# Sch_LVTN.net
KiCad netlist of a schematic drawn in Altium Designer
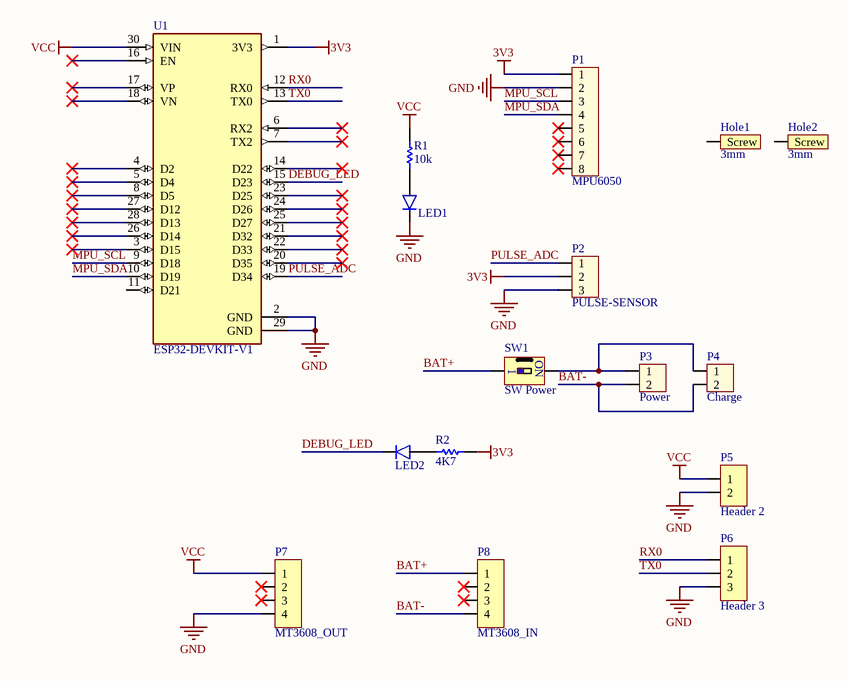
[diagram p0: Sch_LVTN.SchDoc]

(export (version "E")
  (design (tool "Eeschema 10.0.6"))
  (components
    (comp (ref "Hole1") (value "3mm") (footprint "SCREW/3M/7M") (libsource (lib "BKIT4U_LIB") (part "Screw")))
    (comp (ref "Hole2") (value "3mm") (footprint "SCREW/3M/7M") (libsource (lib "BKIT4U_LIB") (part "Screw")))
    (comp (ref "LED1")
      (value "Led")
      (footprint "Led SMD 0805")
      (description "Typical LED")
      (libsource (lib "BKIT4U_LIB") (part "Led"))
    )
    (comp (ref "LED2")
      (value "Led")
      (footprint "Led SMD 0805")
      (description "Typical LED")
      (libsource (lib "BKIT4U_LIB") (part "Led"))
    )
    (comp (ref "P1")
      (value "MPU6050")
      (footprint "CON Header 8")
      (description "Connector 8")
      (libsource (lib "BKIT4U_LIB") (part "Con8"))
    )
    (comp (ref "P2")
      (value "PULSE-SENSOR")
      (footprint "CON Header 3")
      (description "Connector 3")
      (libsource (lib "BKIT4U_LIB") (part "Con3"))
    )
    (comp (ref "P3")
      (value "Power")
      (footprint "CON Header 2")
      (description "Connector 2")
      (libsource (lib "BKIT4U_LIB") (part "Con2"))
    )
    (comp (ref "P4")
      (value "Charge")
      (footprint "CON Header 2 - RA")
      (description "Connector 2")
      (libsource (lib "BKIT4U_LIB") (part "Con2"))
    )
    (comp (ref "P5")
      (value "Header 2")
      (footprint "Header 2")
      (description "Header, 2-Pin")
      (fields (field (name "PUBLISHER") "Altium Limited"))
      (libsource (lib "BKIT4U_LIB") (part "Header 2"))
    )
    (comp (ref "P6")
      (value "Header 3")
      (footprint "Header 3")
      (description "Header, 3-Pin")
      (libsource (lib "BKIT4U_LIB") (part "Header 3"))
    )
    (comp (ref "P7")
      (value "MT3608_OUT")
      (footprint "Header 4")
      (description "Header, 4-Pin")
      (libsource (lib "BKIT4U_LIB") (part "Header 4"))
    )
    (comp (ref "P8")
      (value "MT3608_IN")
      (footprint "Header 4")
      (description "Header, 4-Pin")
      (libsource (lib "BKIT4U_LIB") (part "Header 4"))
    )
    (comp (ref "R1")
      (value "10k")
      (footprint "R 0805 (2012)")
      (description "Resistor")
      (fields (field (name "PUBLISHER") "Altium Limited"))
      (libsource (lib "BKIT4U_LIB") (part "Resistor"))
    )
    (comp (ref "R2")
      (value "4K7")
      (footprint "R 0805 (2012)")
      (description "Resistor")
      (fields (field (name "PUBLISHER") "Altium Limited"))
      (libsource (lib "BKIT4U_LIB") (part "Resistor"))
    )
    (comp (ref "SW1")
      (value "SW Power")
      (footprint "SW/DIP1")
      (libsource (lib "BKIT4U_LIB") (part "SW DIP-1"))
    )
    (comp (ref "U1")
      (value "ESP32-DEVKIT-V1")
      (footprint "MODULE_ESP32_DEVKIT_V1")
      (fields (field (name "MF") "Do it"))
      (libsource (lib "ESP32-DEVKIT-V1") (part "ESP32-DEVKIT-V1"))
    )
  )
  (nets
    (net (code "1") (name "/BAT+") (class "Default")
      (node (ref "P8") (pin "1") (pinfunction "1_1") (pintype "passive"))
      (node (ref "SW1") (pin "1") (pinfunction "1_1") (pintype "passive"))
    )
    (net (code "2") (name "/BAT-") (class "Default")
      (node (ref "P3") (pin "2") (pinfunction "2_2") (pintype "passive"))
      (node (ref "P4") (pin "2") (pinfunction "2_2") (pintype "passive"))
      (node (ref "P8") (pin "4") (pinfunction "4_4") (pintype "passive"))
    )
    (net (code "3") (name "/DEBUG_LED") (class "Default")
      (node (ref "LED2") (pin "2") (pinfunction "K_2") (pintype "passive"))
      (node (ref "U1") (pin "15") (pinfunction "D23_15") (pintype "bidirectional"))
    )
    (net (code "4") (name "/MPU_SCL") (class "Default")
      (node (ref "P1") (pin "3") (pinfunction "3_3") (pintype "passive"))
      (node (ref "U1") (pin "9") (pinfunction "D18_9") (pintype "bidirectional"))
    )
    (net (code "5") (name "/MPU_SDA") (class "Default")
      (node (ref "P1") (pin "4") (pinfunction "4_4") (pintype "passive"))
      (node (ref "U1") (pin "10") (pinfunction "D19_10") (pintype "bidirectional"))
    )
    (net (code "6") (name "/PULSE_ADC") (class "Default")
      (node (ref "P2") (pin "1") (pinfunction "1_1") (pintype "passive"))
      (node (ref "U1") (pin "19") (pinfunction "D34_19") (pintype "bidirectional"))
    )
    (net (code "7") (name "/RX0") (class "Default")
      (node (ref "P6") (pin "1") (pinfunction "1_1") (pintype "passive"))
      (node (ref "U1") (pin "12") (pinfunction "RX0_12") (pintype "input"))
    )
    (net (code "8") (name "/TX0") (class "Default")
      (node (ref "P6") (pin "2") (pinfunction "2_2") (pintype "passive"))
      (node (ref "U1") (pin "13") (pinfunction "TX0_13") (pintype "output"))
    )
    (net (code "9") (name "3V3") (class "Default")
      (node (ref "P1") (pin "1") (pinfunction "1_1") (pintype "passive"))
      (node (ref "P2") (pin "2") (pinfunction "2_2") (pintype "passive"))
      (node (ref "R2") (pin "2") (pinfunction "2_2") (pintype "passive"))
      (node (ref "U1") (pin "1") (pinfunction "3V3_1") (pintype "output"))
    )
    (net (code "10") (name "GND") (class "Default")
      (node (ref "LED1") (pin "2") (pinfunction "K_2") (pintype "passive"))
      (node (ref "P1") (pin "2") (pinfunction "2_2") (pintype "passive"))
      (node (ref "P2") (pin "3") (pinfunction "3_3") (pintype "passive"))
      (node (ref "P5") (pin "2") (pinfunction "2_2") (pintype "passive"))
      (node (ref "P6") (pin "3") (pinfunction "3_3") (pintype "passive"))
      (node (ref "P7") (pin "4") (pinfunction "4_4") (pintype "passive"))
      (node (ref "U1") (pin "2") (pinfunction "GND_2") (pintype "power_in"))
      (node (ref "U1") (pin "29") (pinfunction "GND_29") (pintype "power_in"))
    )
    (net (code "11") (name "Net-(LED1-A)") (class "Default")
      (node (ref "LED1") (pin "1") (pinfunction "A_1") (pintype "passive"))
      (node (ref "R1") (pin "1") (pinfunction "1_1") (pintype "passive"))
    )
    (net (code "12") (name "Net-(LED2-A)") (class "Default")
      (node (ref "LED2") (pin "1") (pinfunction "A_1") (pintype "passive"))
      (node (ref "R2") (pin "1") (pinfunction "1_1") (pintype "passive"))
    )
    (net (code "13") (name "Net-(P3-Pad1)") (class "Default")
      (node (ref "P3") (pin "1") (pinfunction "1_1") (pintype "passive"))
      (node (ref "P4") (pin "1") (pinfunction "1_1") (pintype "passive"))
      (node (ref "SW1") (pin "2") (pinfunction "2_2") (pintype "passive"))
    )
    (net (code "14") (name "VCC") (class "Default")
      (node (ref "P5") (pin "1") (pinfunction "1_1") (pintype "passive"))
      (node (ref "P7") (pin "1") (pinfunction "1_1") (pintype "passive"))
      (node (ref "R1") (pin "2") (pinfunction "2_2") (pintype "passive"))
      (node (ref "U1") (pin "30") (pinfunction "VIN_30") (pintype "input"))
    )
    (net (code "15") (name "unconnected-(Hole1-Screw-Pad1)") (class "Default")
      (node (ref "Hole1") (pin "1") (pinfunction "Screw_1") (pintype "passive"))
    )
    (net (code "16") (name "unconnected-(Hole2-Screw-Pad1)") (class "Default")
      (node (ref "Hole2") (pin "1") (pinfunction "Screw_1") (pintype "passive"))
    )
    (net (code "17") (name "unconnected-(P1-Pad5)") (class "Default")
      (node (ref "P1") (pin "5") (pinfunction "5_5") (pintype "passive+no_connect"))
    )
    (net (code "18") (name "unconnected-(P1-Pad6)") (class "Default")
      (node (ref "P1") (pin "6") (pinfunction "6_6") (pintype "passive+no_connect"))
    )
    (net (code "19") (name "unconnected-(P1-Pad7)") (class "Default")
      (node (ref "P1") (pin "7") (pinfunction "7_7") (pintype "passive+no_connect"))
    )
    (net (code "20") (name "unconnected-(P1-Pad8)") (class "Default")
      (node (ref "P1") (pin "8") (pinfunction "8_8") (pintype "passive+no_connect"))
    )
    (net (code "21") (name "unconnected-(P7-Pad2)") (class "Default")
      (node (ref "P7") (pin "2") (pinfunction "2_2") (pintype "passive+no_connect"))
    )
    (net (code "22") (name "unconnected-(P7-Pad3)") (class "Default")
      (node (ref "P7") (pin "3") (pinfunction "3_3") (pintype "passive+no_connect"))
    )
    (net (code "23") (name "unconnected-(P8-Pad2)") (class "Default")
      (node (ref "P8") (pin "2") (pinfunction "2_2") (pintype "passive+no_connect"))
    )
    (net (code "24") (name "unconnected-(P8-Pad3)") (class "Default")
      (node (ref "P8") (pin "3") (pinfunction "3_3") (pintype "passive+no_connect"))
    )
    (net (code "25") (name "unconnected-(U1-D2-Pad4)") (class "Default")
      (node (ref "U1") (pin "4") (pinfunction "D2_4") (pintype "bidirectional+no_connect"))
    )
    (net (code "26") (name "unconnected-(U1-D4-Pad5)") (class "Default")
      (node (ref "U1") (pin "5") (pinfunction "D4_5") (pintype "bidirectional+no_connect"))
    )
    (net (code "27") (name "unconnected-(U1-D5-Pad8)") (class "Default")
      (node (ref "U1") (pin "8") (pinfunction "D5_8") (pintype "bidirectional+no_connect"))
    )
    (net (code "28") (name "unconnected-(U1-D12-Pad27)") (class "Default")
      (node (ref "U1") (pin "27") (pinfunction "D12_27") (pintype "bidirectional+no_connect"))
    )
    (net (code "29") (name "unconnected-(U1-D13-Pad28)") (class "Default")
      (node (ref "U1") (pin "28") (pinfunction "D13_28") (pintype "bidirectional+no_connect"))
    )
    (net (code "30") (name "unconnected-(U1-D14-Pad26)") (class "Default")
      (node (ref "U1") (pin "26") (pinfunction "D14_26") (pintype "bidirectional+no_connect"))
    )
    (net (code "31") (name "unconnected-(U1-D15-Pad3)") (class "Default")
      (node (ref "U1") (pin "3") (pinfunction "D15_3") (pintype "bidirectional+no_connect"))
    )
    (net (code "32") (name "unconnected-(U1-D21-Pad11)") (class "Default")
      (node (ref "U1") (pin "11") (pinfunction "D21_11") (pintype "bidirectional"))
    )
    (net (code "33") (name "unconnected-(U1-D22-Pad14)") (class "Default")
      (node (ref "U1") (pin "14") (pinfunction "D22_14") (pintype "bidirectional+no_connect"))
    )
    (net (code "34") (name "unconnected-(U1-D25-Pad23)") (class "Default")
      (node (ref "U1") (pin "23") (pinfunction "D25_23") (pintype "bidirectional+no_connect"))
    )
    (net (code "35") (name "unconnected-(U1-D26-Pad24)") (class "Default")
      (node (ref "U1") (pin "24") (pinfunction "D26_24") (pintype "bidirectional+no_connect"))
    )
    (net (code "36") (name "unconnected-(U1-D27-Pad25)") (class "Default")
      (node (ref "U1") (pin "25") (pinfunction "D27_25") (pintype "bidirectional+no_connect"))
    )
    (net (code "37") (name "unconnected-(U1-D32-Pad21)") (class "Default")
      (node (ref "U1") (pin "21") (pinfunction "D32_21") (pintype "bidirectional+no_connect"))
    )
    (net (code "38") (name "unconnected-(U1-D33-Pad22)") (class "Default")
      (node (ref "U1") (pin "22") (pinfunction "D33_22") (pintype "bidirectional+no_connect"))
    )
    (net (code "39") (name "unconnected-(U1-D35-Pad20)") (class "Default")
      (node (ref "U1") (pin "20") (pinfunction "D35_20") (pintype "bidirectional+no_connect"))
    )
    (net (code "40") (name "unconnected-(U1-EN-Pad16)") (class "Default")
      (node (ref "U1") (pin "16") (pinfunction "EN_16") (pintype "input+no_connect"))
    )
    (net (code "41") (name "unconnected-(U1-RX2-Pad6)") (class "Default")
      (node (ref "U1") (pin "6") (pinfunction "RX2_6") (pintype "input+no_connect"))
    )
    (net (code "42") (name "unconnected-(U1-TX2-Pad7)") (class "Default")
      (node (ref "U1") (pin "7") (pinfunction "TX2_7") (pintype "output+no_connect"))
    )
    (net (code "43") (name "unconnected-(U1-VN-Pad18)") (class "Default")
      (node (ref "U1") (pin "18") (pinfunction "VN_18") (pintype "bidirectional+no_connect"))
    )
    (net (code "44") (name "unconnected-(U1-VP-Pad17)") (class "Default")
      (node (ref "U1") (pin "17") (pinfunction "VP_17") (pintype "bidirectional+no_connect"))
    )
  )
)
